# breeze_controller.net
KiCad netlist of a schematic drawn in Altium Designer
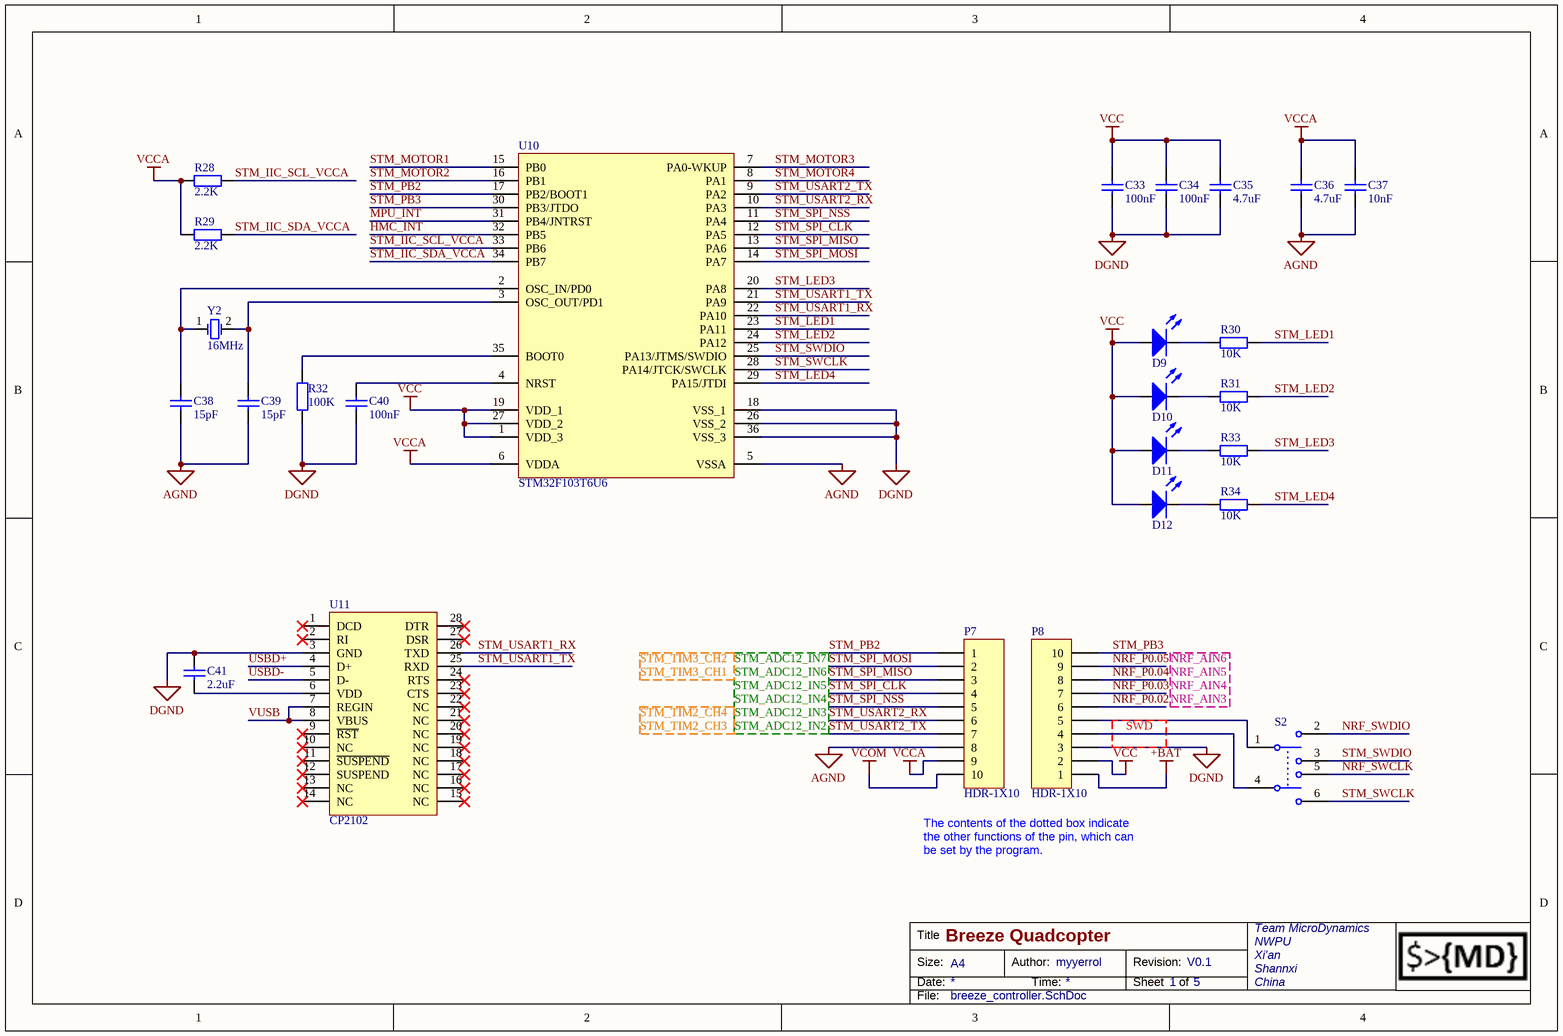
[diagram p0: breeze_controller.SchDoc]

(export (version "E")
  (design (tool "Eeschema 10.0.6"))
  (components
    (comp (ref "C33")
      (value "100nF")
      (footprint "SMD-0603")
      (description "Capacitor")
      (fields (field (name "Comment") "CAP-0603"))
      (libsource (lib "breeze_design_library") (part "CAP-0603"))
    )
    (comp (ref "C34")
      (value "100nF")
      (footprint "SMD-0603")
      (description "Capacitor")
      (fields (field (name "Comment") "CAP-0603"))
      (libsource (lib "breeze_design_library") (part "CAP-0603"))
    )
    (comp (ref "C35")
      (value "4.7uF")
      (footprint "SMD-0603")
      (description "Capacitor")
      (fields (field (name "Comment") "CAP-0603"))
      (libsource (lib "breeze_design_library") (part "CAP-0603"))
    )
    (comp (ref "C36")
      (value "4.7uF")
      (footprint "SMD-0603")
      (description "Capacitor")
      (fields (field (name "Comment") "CAP-0603"))
      (libsource (lib "breeze_design_library") (part "CAP-0603"))
    )
    (comp (ref "C37")
      (value "10nF")
      (footprint "SMD-0603")
      (description "Capacitor")
      (fields (field (name "Comment") "CAP-0603"))
      (libsource (lib "breeze_design_library") (part "CAP-0603"))
    )
    (comp (ref "C38")
      (value "15pF")
      (footprint "SMD-0603")
      (description "Capacitor")
      (fields (field (name "Comment") "CAP-0603"))
      (libsource (lib "breeze_design_library") (part "CAP-0603"))
    )
    (comp (ref "C39")
      (value "15pF")
      (footprint "SMD-0603")
      (description "Capacitor")
      (fields (field (name "Comment") "CAP-0603"))
      (libsource (lib "breeze_design_library") (part "CAP-0603"))
    )
    (comp (ref "C40")
      (value "100nF")
      (footprint "SMD-0603")
      (description "Capacitor")
      (fields (field (name "Comment") "CAP-0603"))
      (libsource (lib "breeze_design_library") (part "CAP-0603"))
    )
    (comp (ref "C41")
      (value "2.2uF")
      (footprint "SMD-0603")
      (description "Capacitor")
      (fields (field (name "Comment") "CAP-0603"))
      (libsource (lib "breeze_design_library") (part "CAP-0603"))
    )
    (comp (ref "D9")
      (value "LED-0603")
      (footprint "SMD-0603")
      (description "LED")
      (libsource (lib "breeze_design_library") (part "LED-0603"))
    )
    (comp (ref "D10")
      (value "LED-0603")
      (footprint "SMD-0603")
      (description "LED")
      (libsource (lib "breeze_design_library") (part "LED-0603"))
    )
    (comp (ref "D11")
      (value "LED-0603")
      (footprint "SMD-0603")
      (description "LED")
      (libsource (lib "breeze_design_library") (part "LED-0603"))
    )
    (comp (ref "D12")
      (value "LED-0603")
      (footprint "SMD-0603")
      (description "LED")
      (libsource (lib "breeze_design_library") (part "LED-0603"))
    )
    (comp (ref "P7")
      (value "HDR-1X10")
      (footprint "HDR-1X10")
      (description "Header 1X10")
      (libsource (lib "breeze_design_library") (part "HDR-1X10"))
    )
    (comp (ref "P8")
      (value "HDR-1X10")
      (footprint "HDR-1X10")
      (description "Header 1X10")
      (libsource (lib "") (part "HDR-1X10_1"))
    )
    (comp (ref "R28")
      (value "2.2K")
      (footprint "SMD-0603")
      (description "Resistor")
      (fields (field (name "Comment") "RES-0603"))
      (libsource (lib "breeze_design_library") (part "RES-0603"))
    )
    (comp (ref "R29")
      (value "2.2K")
      (footprint "SMD-0603")
      (description "Resistor")
      (fields (field (name "Comment") "RES-0603"))
      (libsource (lib "breeze_design_library") (part "RES-0603"))
    )
    (comp (ref "R30")
      (value "10K")
      (footprint "SMD-0603")
      (description "Resistor")
      (fields (field (name "Comment") "RES-0603"))
      (libsource (lib "breeze_design_library") (part "RES-0603"))
    )
    (comp (ref "R31")
      (value "10K")
      (footprint "SMD-0603")
      (description "Resistor")
      (fields (field (name "Comment") "RES-0603"))
      (libsource (lib "breeze_design_library") (part "RES-0603"))
    )
    (comp (ref "R32")
      (value "100K")
      (footprint "SMD-0603")
      (description "Resistor")
      (fields (field (name "Comment") "RES-0603"))
      (libsource (lib "") (part "RES-0603_1"))
    )
    (comp (ref "R33")
      (value "10K")
      (footprint "SMD-0603")
      (description "Resistor")
      (fields (field (name "Comment") "RES-0603"))
      (libsource (lib "breeze_design_library") (part "RES-0603"))
    )
    (comp (ref "R34")
      (value "10K")
      (footprint "SMD-0603")
      (description "Resistor")
      (fields (field (name "Comment") "RES-0603"))
      (libsource (lib "breeze_design_library") (part "RES-0603"))
    )
    (comp (ref "S2")
      (value "MSS-22D18G2")
      (footprint "MSS-22D18G2")
      (description "Double-Pole, Double-Throw Switch")
      (libsource (lib "breeze_design_library") (part "MSS-22D18G2"))
    )
    (comp (ref "U10")
      (value "STM32F103T6U6")
      (footprint "VFQFPN-36")
      (description "ARM Cortex-M3 MCU")
      (libsource (lib "breeze_design_library") (part "STM32F103T6U6"))
    )
    (comp (ref "U11")
      (value "CP2102")
      (footprint "QFN-28")
      (description "Highly-integrated USB-to-UART Bridge Controller")
      (libsource (lib "breeze_design_library") (part "CP2102"))
    )
    (comp (ref "Y2")
      (value "16MHz")
      (footprint "SMD-5032")
      (description "Passive Crystal Oscillator")
      (fields (field (name "Comment") "XTAL-5032"))
      (libsource (lib "breeze_design_library") (part "XTAL-5032"))
    )
  )
  (nets
    (net (code "1") (name "+BAT") (class "Default")
      (node (ref "P8") (pin "1") (pinfunction "1_1") (pintype "passive"))
    )
    (net (code "2") (name "/HMC_INT") (class "Default")
      (node (ref "U10") (pin "32") (pinfunction "PB5_32") (pintype "passive"))
    )
    (net (code "3") (name "/MPU_INT") (class "Default")
      (node (ref "U10") (pin "31") (pinfunction "PB4/JNTRST_31") (pintype "passive"))
    )
    (net (code "4") (name "/NRF_P0.02") (class "Default")
      (node (ref "P8") (pin "6") (pinfunction "6_6") (pintype "passive"))
    )
    (net (code "5") (name "/NRF_P0.03") (class "Default")
      (node (ref "P8") (pin "7") (pinfunction "7_7") (pintype "passive"))
    )
    (net (code "6") (name "/NRF_P0.04") (class "Default")
      (node (ref "P8") (pin "8") (pinfunction "8_8") (pintype "passive"))
    )
    (net (code "7") (name "/NRF_P0.05") (class "Default")
      (node (ref "P8") (pin "9") (pinfunction "9_9") (pintype "passive"))
    )
    (net (code "8") (name "/NRF_SWCLK") (class "Default")
      (node (ref "S2") (pin "5") (pinfunction "5_5") (pintype "passive"))
    )
    (net (code "9") (name "/NRF_SWDIO") (class "Default")
      (node (ref "S2") (pin "2") (pinfunction "2_2") (pintype "passive"))
    )
    (net (code "10") (name "/STM_IIC_SCL_VCCA") (class "Default")
      (node (ref "R28") (pin "2") (pinfunction "2_2") (pintype "passive"))
      (node (ref "U10") (pin "33") (pinfunction "PB6_33") (pintype "passive"))
    )
    (net (code "11") (name "/STM_IIC_SDA_VCCA") (class "Default")
      (node (ref "R29") (pin "2") (pinfunction "2_2") (pintype "passive"))
      (node (ref "U10") (pin "34") (pinfunction "PB7_34") (pintype "passive"))
    )
    (net (code "12") (name "/STM_LED1") (class "Default")
      (node (ref "R30") (pin "2") (pinfunction "2_2") (pintype "passive"))
      (node (ref "U10") (pin "23") (pinfunction "PA11_23") (pintype "passive"))
    )
    (net (code "13") (name "/STM_LED2") (class "Default")
      (node (ref "R31") (pin "2") (pinfunction "2_2") (pintype "passive"))
      (node (ref "U10") (pin "24") (pinfunction "PA12_24") (pintype "passive"))
    )
    (net (code "14") (name "/STM_LED3") (class "Default")
      (node (ref "R33") (pin "2") (pinfunction "2_2") (pintype "passive"))
      (node (ref "U10") (pin "20") (pinfunction "PA8_20") (pintype "passive"))
    )
    (net (code "15") (name "/STM_LED4") (class "Default")
      (node (ref "R34") (pin "2") (pinfunction "2_2") (pintype "passive"))
      (node (ref "U10") (pin "29") (pinfunction "PA15/JTDI_29") (pintype "passive"))
    )
    (net (code "16") (name "/STM_MOTOR1") (class "Default")
      (node (ref "U10") (pin "15") (pinfunction "PB0_15") (pintype "passive"))
    )
    (net (code "17") (name "/STM_MOTOR2") (class "Default")
      (node (ref "U10") (pin "16") (pinfunction "PB1_16") (pintype "passive"))
    )
    (net (code "18") (name "/STM_MOTOR3") (class "Default")
      (node (ref "U10") (pin "7") (pinfunction "PA0-WKUP_7") (pintype "passive"))
    )
    (net (code "19") (name "/STM_MOTOR4") (class "Default")
      (node (ref "U10") (pin "8") (pinfunction "PA1_8") (pintype "passive"))
    )
    (net (code "20") (name "/STM_PB2") (class "Default")
      (node (ref "P7") (pin "1") (pinfunction "1_1") (pintype "passive"))
      (node (ref "U10") (pin "17") (pinfunction "PB2/BOOT1_17") (pintype "passive"))
    )
    (net (code "21") (name "/STM_PB3") (class "Default")
      (node (ref "P8") (pin "10") (pinfunction "10_10") (pintype "passive"))
      (node (ref "U10") (pin "30") (pinfunction "PB3/JTDO_30") (pintype "passive"))
    )
    (net (code "22") (name "/STM_SPI_CLK") (class "Default")
      (node (ref "P7") (pin "4") (pinfunction "4_4") (pintype "passive"))
      (node (ref "U10") (pin "12") (pinfunction "PA5_12") (pintype "passive"))
    )
    (net (code "23") (name "/STM_SPI_MISO") (class "Default")
      (node (ref "P7") (pin "3") (pinfunction "3_3") (pintype "passive"))
      (node (ref "U10") (pin "13") (pinfunction "PA6_13") (pintype "passive"))
    )
    (net (code "24") (name "/STM_SPI_MOSI") (class "Default")
      (node (ref "P7") (pin "2") (pinfunction "2_2") (pintype "passive"))
      (node (ref "U10") (pin "14") (pinfunction "PA7_14") (pintype "passive"))
    )
    (net (code "25") (name "/STM_SPI_NSS") (class "Default")
      (node (ref "P7") (pin "5") (pinfunction "5_5") (pintype "passive"))
      (node (ref "U10") (pin "11") (pinfunction "PA4_11") (pintype "passive"))
    )
    (net (code "26") (name "/STM_SWCLK") (class "Default")
      (node (ref "S2") (pin "6") (pinfunction "6_6") (pintype "passive"))
      (node (ref "U10") (pin "28") (pinfunction "PA14/JTCK/SWCLK_28") (pintype "passive"))
    )
    (net (code "27") (name "/STM_SWDIO") (class "Default")
      (node (ref "S2") (pin "3") (pinfunction "3_3") (pintype "passive"))
      (node (ref "U10") (pin "25") (pinfunction "PA13/JTMS/SWDIO_25") (pintype "passive"))
    )
    (net (code "28") (name "/STM_USART1_RX") (class "Default")
      (node (ref "U10") (pin "22") (pinfunction "PA10_22") (pintype "passive"))
      (node (ref "U11") (pin "26") (pinfunction "TXD_26") (pintype "passive"))
    )
    (net (code "29") (name "/STM_USART1_TX") (class "Default")
      (node (ref "U10") (pin "21") (pinfunction "PA9_21") (pintype "passive"))
      (node (ref "U11") (pin "25") (pinfunction "RXD_25") (pintype "passive"))
    )
    (net (code "30") (name "/STM_USART2_RX") (class "Default")
      (node (ref "P7") (pin "6") (pinfunction "6_6") (pintype "passive"))
      (node (ref "U10") (pin "10") (pinfunction "PA3_10") (pintype "passive"))
    )
    (net (code "31") (name "/STM_USART2_TX") (class "Default")
      (node (ref "P7") (pin "7") (pinfunction "7_7") (pintype "passive"))
      (node (ref "U10") (pin "9") (pinfunction "PA2_9") (pintype "passive"))
    )
    (net (code "32") (name "/USBD+") (class "Default")
      (node (ref "U11") (pin "4") (pinfunction "D+_4") (pintype "passive"))
    )
    (net (code "33") (name "/USBD-") (class "Default")
      (node (ref "U11") (pin "5") (pinfunction "D-_5") (pintype "passive"))
    )
    (net (code "34") (name "/VUSB") (class "Default")
      (node (ref "U11") (pin "7") (pinfunction "REGIN_7") (pintype "passive"))
      (node (ref "U11") (pin "8") (pinfunction "VBUS_8") (pintype "passive"))
    )
    (net (code "35") (name "AGND") (class "Default")
      (node (ref "C36") (pin "2") (pinfunction "2_2") (pintype "passive"))
      (node (ref "C37") (pin "2") (pinfunction "2_2") (pintype "passive"))
      (node (ref "C38") (pin "2") (pinfunction "2_2") (pintype "passive"))
      (node (ref "C39") (pin "2") (pinfunction "2_2") (pintype "passive"))
      (node (ref "P7") (pin "8") (pinfunction "8_8") (pintype "passive"))
      (node (ref "U10") (pin "5") (pinfunction "VSSA_5") (pintype "passive"))
    )
    (net (code "36") (name "DGND") (class "Default")
      (node (ref "C33") (pin "2") (pinfunction "2_2") (pintype "passive"))
      (node (ref "C34") (pin "2") (pinfunction "2_2") (pintype "passive"))
      (node (ref "C35") (pin "2") (pinfunction "2_2") (pintype "passive"))
      (node (ref "C40") (pin "2") (pinfunction "2_2") (pintype "passive"))
      (node (ref "C41") (pin "2") (pinfunction "2_2") (pintype "passive"))
      (node (ref "P8") (pin "3") (pinfunction "3_3") (pintype "passive"))
      (node (ref "R32") (pin "2") (pinfunction "2_2") (pintype "passive"))
      (node (ref "U10") (pin "18") (pinfunction "VSS_1_18") (pintype "passive"))
      (node (ref "U10") (pin "26") (pinfunction "VSS_2_26") (pintype "passive"))
      (node (ref "U10") (pin "36") (pinfunction "VSS_3_36") (pintype "passive"))
      (node (ref "U11") (pin "3") (pinfunction "GND_3") (pintype "passive"))
    )
    (net (code "37") (name "Net-(D9-K)") (class "Default")
      (node (ref "D9") (pin "2") (pinfunction "K_2") (pintype "passive"))
      (node (ref "R30") (pin "1") (pinfunction "1_1") (pintype "passive"))
    )
    (net (code "38") (name "Net-(D10-K)") (class "Default")
      (node (ref "D10") (pin "2") (pinfunction "K_2") (pintype "passive"))
      (node (ref "R31") (pin "1") (pinfunction "1_1") (pintype "passive"))
    )
    (net (code "39") (name "Net-(D11-K)") (class "Default")
      (node (ref "D11") (pin "2") (pinfunction "K_2") (pintype "passive"))
      (node (ref "R33") (pin "1") (pinfunction "1_1") (pintype "passive"))
    )
    (net (code "40") (name "Net-(D12-K)") (class "Default")
      (node (ref "D12") (pin "2") (pinfunction "K_2") (pintype "passive"))
      (node (ref "R34") (pin "1") (pinfunction "1_1") (pintype "passive"))
    )
    (net (code "41") (name "Net-(P8-Pad4)") (class "Default")
      (node (ref "P8") (pin "4") (pinfunction "4_4") (pintype "passive"))
      (node (ref "S2") (pin "4") (pinfunction "4_4") (pintype "passive"))
    )
    (net (code "42") (name "Net-(P8-Pad5)") (class "Default")
      (node (ref "P8") (pin "5") (pinfunction "5_5") (pintype "passive"))
      (node (ref "S2") (pin "1") (pinfunction "1_1") (pintype "passive"))
    )
    (net (code "43") (name "Net-(U10-BOOT0)") (class "Default")
      (node (ref "R32") (pin "1") (pinfunction "1_1") (pintype "passive"))
      (node (ref "U10") (pin "35") (pinfunction "BOOT0_35") (pintype "passive"))
    )
    (net (code "44") (name "Net-(U10-NRST)") (class "Default")
      (node (ref "C40") (pin "1") (pinfunction "1_1") (pintype "passive"))
      (node (ref "U10") (pin "4") (pinfunction "NRST_4") (pintype "passive"))
    )
    (net (code "45") (name "Net-(U10-OSC_IN{slash}PD0)") (class "Default")
      (node (ref "C38") (pin "1") (pinfunction "1_1") (pintype "passive"))
      (node (ref "U10") (pin "2") (pinfunction "OSC_IN/PD0_2") (pintype "passive"))
      (node (ref "Y2") (pin "1") (pinfunction "OSC1_1") (pintype "passive"))
    )
    (net (code "46") (name "Net-(U10-OSC_OUT{slash}PD1)") (class "Default")
      (node (ref "C39") (pin "1") (pinfunction "1_1") (pintype "passive"))
      (node (ref "U10") (pin "3") (pinfunction "OSC_OUT/PD1_3") (pintype "passive"))
      (node (ref "Y2") (pin "2") (pinfunction "OSC2_2") (pintype "passive"))
    )
    (net (code "47") (name "Net-(U11-VDD)") (class "Default")
      (node (ref "C41") (pin "1") (pinfunction "1_1") (pintype "passive"))
      (node (ref "U11") (pin "6") (pinfunction "VDD_6") (pintype "passive"))
    )
    (net (code "48") (name "VCC") (class "Default")
      (node (ref "C33") (pin "1") (pinfunction "1_1") (pintype "passive"))
      (node (ref "C34") (pin "1") (pinfunction "1_1") (pintype "passive"))
      (node (ref "C35") (pin "1") (pinfunction "1_1") (pintype "passive"))
      (node (ref "D10") (pin "1") (pinfunction "A_1") (pintype "passive"))
      (node (ref "D11") (pin "1") (pinfunction "A_1") (pintype "passive"))
      (node (ref "D12") (pin "1") (pinfunction "A_1") (pintype "passive"))
      (node (ref "D9") (pin "1") (pinfunction "A_1") (pintype "passive"))
      (node (ref "P8") (pin "2") (pinfunction "2_2") (pintype "passive"))
      (node (ref "U10") (pin "1") (pinfunction "VDD_3_1") (pintype "passive"))
      (node (ref "U10") (pin "19") (pinfunction "VDD_1_19") (pintype "passive"))
      (node (ref "U10") (pin "27") (pinfunction "VDD_2_27") (pintype "passive"))
    )
    (net (code "49") (name "VCCA") (class "Default")
      (node (ref "C36") (pin "1") (pinfunction "1_1") (pintype "passive"))
      (node (ref "C37") (pin "1") (pinfunction "1_1") (pintype "passive"))
      (node (ref "P7") (pin "9") (pinfunction "9_9") (pintype "passive"))
      (node (ref "R28") (pin "1") (pinfunction "1_1") (pintype "passive"))
      (node (ref "R29") (pin "1") (pinfunction "1_1") (pintype "passive"))
      (node (ref "U10") (pin "6") (pinfunction "VDDA_6") (pintype "passive"))
    )
    (net (code "50") (name "VCOM") (class "Default")
      (node (ref "P7") (pin "10") (pinfunction "10_10") (pintype "passive"))
    )
    (net (code "51") (name "unconnected-(U11-CTS-Pad23)") (class "Default")
      (node (ref "U11") (pin "23") (pinfunction "CTS_23") (pintype "passive+no_connect"))
    )
    (net (code "52") (name "unconnected-(U11-DCD-Pad1)") (class "Default")
      (node (ref "U11") (pin "1") (pinfunction "DCD_1") (pintype "passive+no_connect"))
    )
    (net (code "53") (name "unconnected-(U11-DSR-Pad27)") (class "Default")
      (node (ref "U11") (pin "27") (pinfunction "DSR_27") (pintype "passive+no_connect"))
    )
    (net (code "54") (name "unconnected-(U11-DTR-Pad28)") (class "Default")
      (node (ref "U11") (pin "28") (pinfunction "DTR_28") (pintype "passive+no_connect"))
    )
    (net (code "55") (name "unconnected-(U11-NC-Pad10)") (class "Default")
      (node (ref "U11") (pin "10") (pinfunction "NC_10") (pintype "passive+no_connect"))
    )
    (net (code "56") (name "unconnected-(U11-NC-Pad13)") (class "Default")
      (node (ref "U11") (pin "13") (pinfunction "NC_13") (pintype "passive+no_connect"))
    )
    (net (code "57") (name "unconnected-(U11-NC-Pad14)") (class "Default")
      (node (ref "U11") (pin "14") (pinfunction "NC_14") (pintype "passive+no_connect"))
    )
    (net (code "58") (name "unconnected-(U11-NC-Pad15)") (class "Default")
      (node (ref "U11") (pin "15") (pinfunction "NC_15") (pintype "passive+no_connect"))
    )
    (net (code "59") (name "unconnected-(U11-NC-Pad16)") (class "Default")
      (node (ref "U11") (pin "16") (pinfunction "NC_16") (pintype "passive+no_connect"))
    )
    (net (code "60") (name "unconnected-(U11-NC-Pad17)") (class "Default")
      (node (ref "U11") (pin "17") (pinfunction "NC_17") (pintype "passive+no_connect"))
    )
    (net (code "61") (name "unconnected-(U11-NC-Pad18)") (class "Default")
      (node (ref "U11") (pin "18") (pinfunction "NC_18") (pintype "passive+no_connect"))
    )
    (net (code "62") (name "unconnected-(U11-NC-Pad19)") (class "Default")
      (node (ref "U11") (pin "19") (pinfunction "NC_19") (pintype "passive+no_connect"))
    )
    (net (code "63") (name "unconnected-(U11-NC-Pad20)") (class "Default")
      (node (ref "U11") (pin "20") (pinfunction "NC_20") (pintype "passive+no_connect"))
    )
    (net (code "64") (name "unconnected-(U11-NC-Pad21)") (class "Default")
      (node (ref "U11") (pin "21") (pinfunction "NC_21") (pintype "passive+no_connect"))
    )
    (net (code "65") (name "unconnected-(U11-NC-Pad22)") (class "Default")
      (node (ref "U11") (pin "22") (pinfunction "NC_22") (pintype "passive+no_connect"))
    )
    (net (code "66") (name "unconnected-(U11-RI-Pad2)") (class "Default")
      (node (ref "U11") (pin "2") (pinfunction "RI_2") (pintype "passive+no_connect"))
    )
    (net (code "67") (name "unconnected-(U11-RTS-Pad24)") (class "Default")
      (node (ref "U11") (pin "24") (pinfunction "RTS_24") (pintype "passive+no_connect"))
    )
    (net (code "68") (name "unconnected-(U11-SUSPEND-Pad12)") (class "Default")
      (node (ref "U11") (pin "12") (pinfunction "SUSPEND_12") (pintype "passive+no_connect"))
    )
    (net (code "69") (name "unconnected-(U11-~{RST}-Pad9)") (class "Default")
      (node (ref "U11") (pin "9") (pinfunction "~{RST}_9") (pintype "passive+no_connect"))
    )
    (net (code "70") (name "unconnected-(U11-~{SUSPEND}-Pad11)") (class "Default")
      (node (ref "U11") (pin "11") (pinfunction "~{SUSPEND}_11") (pintype "passive+no_connect"))
    )
  )
)
